# CAN_FB_V02.net
KiCad netlist of a schematic drawn in EAGLE
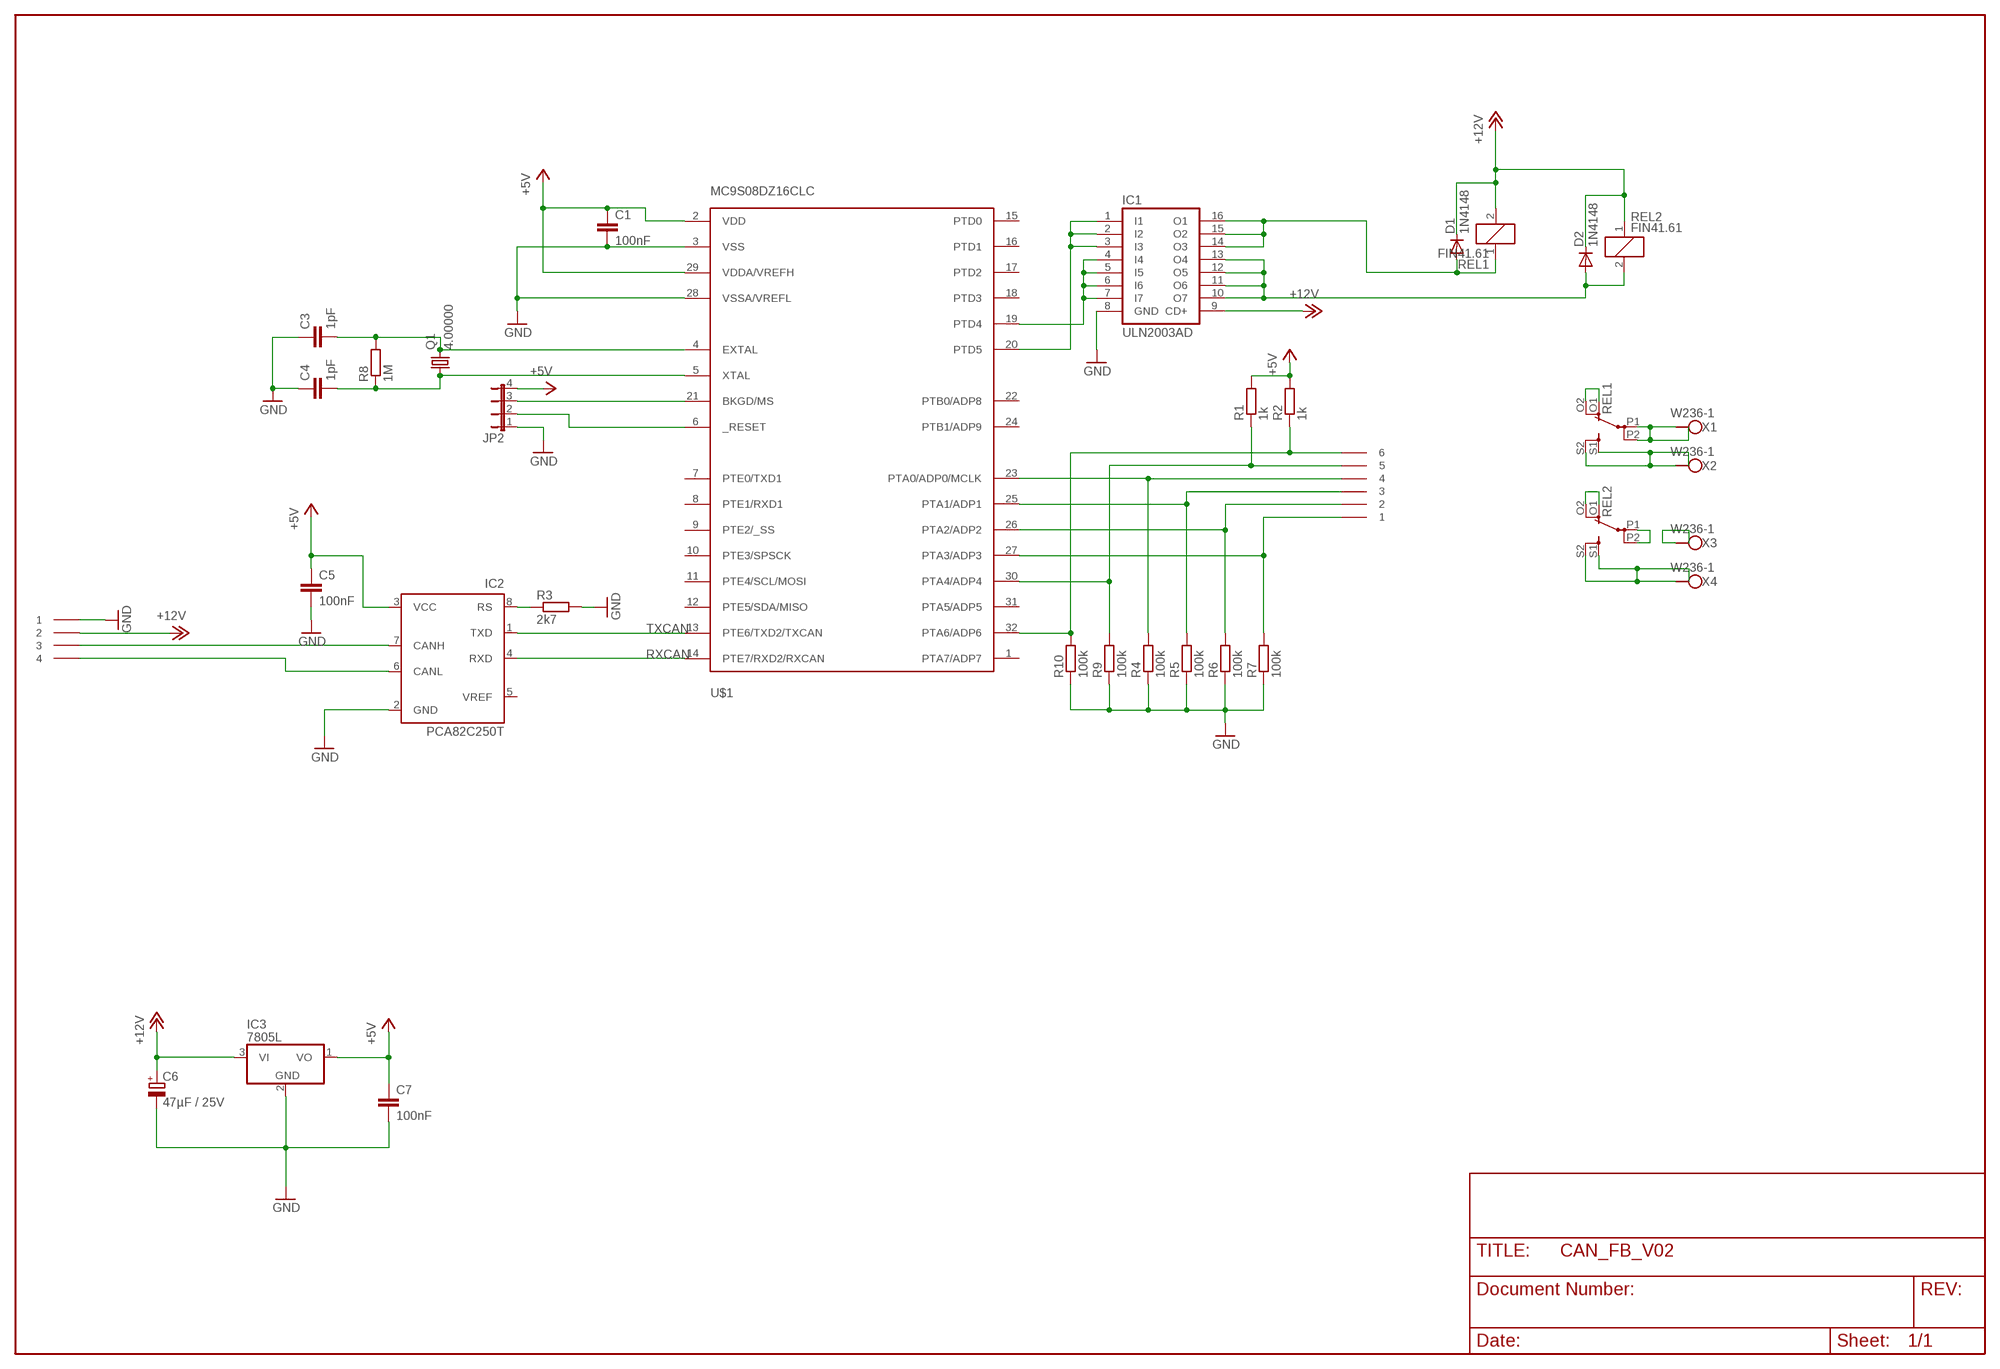
[diagram p0: schematic, sheet 1]

(export (version "E")
  (design (tool "Eeschema 10.0.6"))
  (components
    (comp (ref "C1")
      (value "100nF")
      (footprint "eagle-import:C0805K")
      (libsource (lib "eagle-import") (part "C-EUC0805K"))
    )
    (comp (ref "C3")
      (value "1pF")
      (footprint "eagle-import:C0805K")
      (libsource (lib "eagle-import") (part "C-EUC0805K"))
    )
    (comp (ref "C4")
      (value "1pF")
      (footprint "eagle-import:C0805K")
      (libsource (lib "eagle-import") (part "C-EUC0805K"))
    )
    (comp (ref "C5")
      (value "100nF")
      (footprint "eagle-import:C0805")
      (libsource (lib "eagle-import") (part "C-EUC0805"))
    )
    (comp (ref "C6")
      (value "47µF / 25V")
      (footprint "eagle-import:E2-5")
      (libsource (lib "eagle-import") (part "CPOL-EUE2-5"))
    )
    (comp (ref "C7")
      (value "100nF")
      (footprint "eagle-import:C0805K")
      (libsource (lib "eagle-import") (part "C-EUC0805K"))
    )
    (comp (ref "D1")
      (value "1N4148")
      (footprint "eagle-import:SOD80C")
      (libsource (lib "eagle-import") (part "DIODE-SOD80C"))
    )
    (comp (ref "D2")
      (value "1N4148")
      (footprint "eagle-import:SOD80C")
      (libsource (lib "eagle-import") (part "DIODE-SOD80C"))
    )
    (comp (ref "IC1")
      (value "ULN2003AD")
      (footprint "eagle-import:SO16")
      (libsource (lib "eagle-import") (part "ULN2003AD"))
    )
    (comp (ref "IC2")
      (value "PCA82C250T")
      (footprint "eagle-import:SO8")
      (libsource (lib "eagle-import") (part "PCA82C250T"))
    )
    (comp (ref "IC3")
      (value "7805L")
      (footprint "eagle-import:TO92")
      (libsource (lib "eagle-import") (part "78L05"))
    )
    (comp (ref "JP2")
      (value "JP4E")
      (footprint "eagle-import:JP4")
      (libsource (lib "eagle-import") (part "JP4E"))
    )
    (comp (ref "KL1")
      (value "AST021-04")
      (footprint "eagle-import:AST021-04")
      (libsource (lib "eagle-import") (part "AST021-04"))
    )
    (comp (ref "KL2")
      (value "AST021-06")
      (footprint "eagle-import:AST021-06")
      (libsource (lib "eagle-import") (part "AST021-06"))
    )
    (comp (ref "Q1")
      (value "4.00000")
      (footprint "eagle-import:HC49U-V")
      (libsource (lib "eagle-import") (part "CRYTALHC49U-V"))
    )
    (comp (ref "R1")
      (value "1k")
      (footprint "eagle-import:R0805")
      (libsource (lib "eagle-import") (part "R-EU_R0805"))
    )
    (comp (ref "R2")
      (value "1k")
      (footprint "eagle-import:R0805")
      (libsource (lib "eagle-import") (part "R-EU_R0805"))
    )
    (comp (ref "R3")
      (value "2k7")
      (footprint "eagle-import:R0805")
      (libsource (lib "eagle-import") (part "R-EU_R0805"))
    )
    (comp (ref "R4")
      (value "100k")
      (footprint "eagle-import:R0805")
      (libsource (lib "eagle-import") (part "R-EU_R0805"))
    )
    (comp (ref "R5")
      (value "100k")
      (footprint "eagle-import:R0805")
      (libsource (lib "eagle-import") (part "R-EU_R0805"))
    )
    (comp (ref "R6")
      (value "100k")
      (footprint "eagle-import:R0805")
      (libsource (lib "eagle-import") (part "R-EU_R0805"))
    )
    (comp (ref "R7")
      (value "100k")
      (footprint "eagle-import:R0805")
      (libsource (lib "eagle-import") (part "R-EU_R0805"))
    )
    (comp (ref "R8")
      (value "1M")
      (footprint "eagle-import:R0805")
      (libsource (lib "eagle-import") (part "R-EU_R0805"))
    )
    (comp (ref "R9")
      (value "100k")
      (footprint "eagle-import:R0805")
      (libsource (lib "eagle-import") (part "R-EU_R0805"))
    )
    (comp (ref "R10")
      (value "100k")
      (footprint "eagle-import:R0805")
      (libsource (lib "eagle-import") (part "R-EU_R0805"))
    )
    (comp (ref "REL1")
      (value "FIN41.61")
      (footprint "eagle-import:FIN41")
      (libsource (lib "eagle-import") (part "FIN41.61"))
    )
    (comp (ref "REL2")
      (value "FIN41.61")
      (footprint "eagle-import:FIN41")
      (libsource (lib "eagle-import") (part "FIN41.61"))
    )
    (comp (ref "U$1")
      (value "MC9S08DZ16CLC")
      (footprint "eagle-import:LQFP32")
      (libsource (lib "eagle-import") (part "MC9S08DZ16CLC"))
    )
    (comp (ref "X1")
      (value "W236-1")
      (footprint "eagle-import:W236-1")
      (libsource (lib "eagle-import") (part "W236-1"))
    )
    (comp (ref "X2")
      (value "W236-1")
      (footprint "eagle-import:W236-1")
      (libsource (lib "eagle-import") (part "W236-1"))
    )
    (comp (ref "X3")
      (value "W236-1")
      (footprint "eagle-import:W236-1")
      (libsource (lib "eagle-import") (part "W236-1"))
    )
    (comp (ref "X4")
      (value "W236-1")
      (footprint "eagle-import:W236-1")
      (libsource (lib "eagle-import") (part "W236-1"))
    )
  )
  (nets
    (net (code "1") (name "+5V") (class "Default")
      (node (ref "C1") (pin "1") (pinfunction "1_1") (pintype "passive"))
      (node (ref "C5") (pin "1") (pinfunction "1_1") (pintype "passive"))
      (node (ref "C7") (pin "1") (pinfunction "1_1") (pintype "passive"))
      (node (ref "IC2") (pin "3") (pinfunction "VCC_3") (pintype "power_in"))
      (node (ref "IC3") (pin "1") (pinfunction "VO_1") (pintype "passive"))
      (node (ref "JP2") (pin "4") (pinfunction "4_4") (pintype "passive"))
      (node (ref "R1") (pin "2") (pinfunction "2_2") (pintype "passive"))
      (node (ref "R2") (pin "2") (pinfunction "2_2") (pintype "passive"))
      (node (ref "U$1") (pin "2") (pinfunction "VDD_2") (pintype "power_in"))
      (node (ref "U$1") (pin "29") (pinfunction "VDDA/VREFH_29") (pintype "power_in"))
    )
    (net (code "2") (name "+12V") (class "Default")
      (node (ref "C6") (pin "+") (pinfunction "+_+") (pintype "passive"))
      (node (ref "D1") (pin "C") (pinfunction "C_C") (pintype "passive"))
      (node (ref "D2") (pin "C") (pinfunction "C_C") (pintype "passive"))
      (node (ref "IC1") (pin "9") (pinfunction "CD+_9") (pintype "passive"))
      (node (ref "IC3") (pin "3") (pinfunction "VI_3") (pintype "input"))
      (node (ref "KL1") (pin "P$2") (pinfunction "2_P$2") (pintype "bidirectional"))
      (node (ref "REL1") (pin "2") (pinfunction "2_2") (pintype "passive"))
      (node (ref "REL2") (pin "1") (pinfunction "1_1") (pintype "passive"))
    )
    (net (code "3") (name "/RXCAN") (class "Default")
      (node (ref "IC2") (pin "4") (pinfunction "RXD_4") (pintype "output"))
      (node (ref "U$1") (pin "14") (pinfunction "PTE7/RXD2/RXCAN_14") (pintype "input"))
    )
    (net (code "4") (name "/TXCAN") (class "Default")
      (node (ref "IC2") (pin "1") (pinfunction "TXD_1") (pintype "input"))
      (node (ref "U$1") (pin "13") (pinfunction "PTE6/TXD2/TXCAN_13") (pintype "output"))
    )
    (net (code "5") (name "GND") (class "Default")
      (node (ref "C1") (pin "2") (pinfunction "2_2") (pintype "passive"))
      (node (ref "C3") (pin "1") (pinfunction "1_1") (pintype "passive"))
      (node (ref "C4") (pin "1") (pinfunction "1_1") (pintype "passive"))
      (node (ref "C5") (pin "2") (pinfunction "2_2") (pintype "passive"))
      (node (ref "C6") (pin "-") (pinfunction "-_-") (pintype "passive"))
      (node (ref "C7") (pin "2") (pinfunction "2_2") (pintype "passive"))
      (node (ref "IC1") (pin "8") (pinfunction "GND_8") (pintype "power_in"))
      (node (ref "IC2") (pin "2") (pinfunction "GND_2") (pintype "power_in"))
      (node (ref "IC3") (pin "2") (pinfunction "GND_2") (pintype "passive"))
      (node (ref "JP2") (pin "1") (pinfunction "1_1") (pintype "passive"))
      (node (ref "KL1") (pin "P$1") (pinfunction "1_P$1") (pintype "bidirectional"))
      (node (ref "R10") (pin "1") (pinfunction "1_1") (pintype "passive"))
      (node (ref "R3") (pin "2") (pinfunction "2_2") (pintype "passive"))
      (node (ref "R4") (pin "1") (pinfunction "1_1") (pintype "passive"))
      (node (ref "R5") (pin "1") (pinfunction "1_1") (pintype "passive"))
      (node (ref "R6") (pin "1") (pinfunction "1_1") (pintype "passive"))
      (node (ref "R7") (pin "1") (pinfunction "1_1") (pintype "passive"))
      (node (ref "R9") (pin "1") (pinfunction "1_1") (pintype "passive"))
      (node (ref "U$1") (pin "28") (pinfunction "VSSA/VREFL_28") (pintype "power_in"))
      (node (ref "U$1") (pin "3") (pinfunction "VSS_3") (pintype "power_in"))
    )
    (net (code "6") (name "Net-(IC1-I1)") (class "Default")
      (node (ref "IC1") (pin "1") (pinfunction "I1_1") (pintype "input"))
      (node (ref "IC1") (pin "2") (pinfunction "I2_2") (pintype "input"))
      (node (ref "IC1") (pin "3") (pinfunction "I3_3") (pintype "input"))
      (node (ref "U$1") (pin "20") (pinfunction "PTD5_20") (pintype "bidirectional"))
    )
    (net (code "7") (name "Net-(IC1-I4)") (class "Default")
      (node (ref "IC1") (pin "4") (pinfunction "I4_4") (pintype "input"))
      (node (ref "IC1") (pin "5") (pinfunction "I5_5") (pintype "input"))
      (node (ref "IC1") (pin "6") (pinfunction "I6_6") (pintype "input"))
      (node (ref "IC1") (pin "7") (pinfunction "I7_7") (pintype "input"))
      (node (ref "U$1") (pin "19") (pinfunction "PTD4_19") (pintype "bidirectional"))
    )
    (net (code "8") (name "Net-(IC1-O1)") (class "Default")
      (node (ref "D1") (pin "A") (pinfunction "A_A") (pintype "passive"))
      (node (ref "IC1") (pin "14") (pinfunction "O3_14") (pintype "open_collector"))
      (node (ref "IC1") (pin "15") (pinfunction "O2_15") (pintype "open_collector"))
      (node (ref "IC1") (pin "16") (pinfunction "O1_16") (pintype "open_collector"))
      (node (ref "REL1") (pin "1") (pinfunction "1_1") (pintype "passive"))
    )
    (net (code "9") (name "Net-(IC1-O4)") (class "Default")
      (node (ref "D2") (pin "A") (pinfunction "A_A") (pintype "passive"))
      (node (ref "IC1") (pin "10") (pinfunction "O7_10") (pintype "open_collector"))
      (node (ref "IC1") (pin "11") (pinfunction "O6_11") (pintype "open_collector"))
      (node (ref "IC1") (pin "12") (pinfunction "O5_12") (pintype "open_collector"))
      (node (ref "IC1") (pin "13") (pinfunction "O4_13") (pintype "open_collector"))
      (node (ref "REL2") (pin "2") (pinfunction "2_2") (pintype "passive"))
    )
    (net (code "10") (name "Net-(IC2-CANH)") (class "Default")
      (node (ref "IC2") (pin "7") (pinfunction "CANH_7") (pintype "bidirectional"))
      (node (ref "KL1") (pin "P$3") (pinfunction "3_P$3") (pintype "bidirectional"))
    )
    (net (code "11") (name "Net-(IC2-CANL)") (class "Default")
      (node (ref "IC2") (pin "6") (pinfunction "CANL_6") (pintype "bidirectional"))
      (node (ref "KL1") (pin "P$4") (pinfunction "4_P$4") (pintype "bidirectional"))
    )
    (net (code "12") (name "Net-(IC2-RS)") (class "Default")
      (node (ref "IC2") (pin "8") (pinfunction "RS_8") (pintype "input"))
      (node (ref "R3") (pin "1") (pinfunction "1_1") (pintype "passive"))
    )
    (net (code "13") (name "Net-(KL2-1)") (class "Default")
      (node (ref "KL2") (pin "P$1") (pinfunction "1_P$1") (pintype "bidirectional"))
      (node (ref "R7") (pin "2") (pinfunction "2_2") (pintype "passive"))
      (node (ref "U$1") (pin "27") (pinfunction "PTA3/ADP3_27") (pintype "bidirectional"))
    )
    (net (code "14") (name "Net-(KL2-2)") (class "Default")
      (node (ref "KL2") (pin "P$2") (pinfunction "2_P$2") (pintype "bidirectional"))
      (node (ref "R6") (pin "2") (pinfunction "2_2") (pintype "passive"))
      (node (ref "U$1") (pin "26") (pinfunction "PTA2/ADP2_26") (pintype "bidirectional"))
    )
    (net (code "15") (name "Net-(KL2-3)") (class "Default")
      (node (ref "KL2") (pin "P$3") (pinfunction "3_P$3") (pintype "bidirectional"))
      (node (ref "R5") (pin "2") (pinfunction "2_2") (pintype "passive"))
      (node (ref "U$1") (pin "25") (pinfunction "PTA1/ADP1_25") (pintype "bidirectional"))
    )
    (net (code "16") (name "Net-(KL2-4)") (class "Default")
      (node (ref "KL2") (pin "P$4") (pinfunction "4_P$4") (pintype "bidirectional"))
      (node (ref "R4") (pin "2") (pinfunction "2_2") (pintype "passive"))
      (node (ref "U$1") (pin "23") (pinfunction "PTA0/ADP0/MCLK_23") (pintype "bidirectional"))
    )
    (net (code "17") (name "Net-(KL2-5)") (class "Default")
      (node (ref "KL2") (pin "P$5") (pinfunction "5_P$5") (pintype "bidirectional"))
      (node (ref "R1") (pin "1") (pinfunction "1_1") (pintype "passive"))
      (node (ref "R9") (pin "2") (pinfunction "2_2") (pintype "passive"))
      (node (ref "U$1") (pin "30") (pinfunction "PTA4/ADP4_30") (pintype "bidirectional"))
    )
    (net (code "18") (name "Net-(KL2-6)") (class "Default")
      (node (ref "KL2") (pin "P$6") (pinfunction "6_P$6") (pintype "bidirectional"))
      (node (ref "R10") (pin "2") (pinfunction "2_2") (pintype "passive"))
      (node (ref "R2") (pin "1") (pinfunction "1_1") (pintype "passive"))
      (node (ref "U$1") (pin "32") (pinfunction "PTA6/ADP6_32") (pintype "bidirectional"))
    )
    (net (code "19") (name "Net-(REL1B-O-PadO1)") (class "Default")
      (node (ref "REL1") (pin "O1") (pinfunction "O_O1") (pintype "passive"))
      (node (ref "REL1") (pin "O2") (pinfunction "O_O2") (pintype "passive"))
    )
    (net (code "20") (name "Net-(REL2B-O-PadO1)") (class "Default")
      (node (ref "REL2") (pin "O1") (pinfunction "O_O1") (pintype "passive"))
      (node (ref "REL2") (pin "O2") (pinfunction "O_O2") (pintype "passive"))
    )
    (net (code "21") (name "Net-(REL2B-P-PadP1)") (class "Default")
      (node (ref "REL2") (pin "P1") (pinfunction "P_P1") (pintype "passive"))
      (node (ref "REL2") (pin "P2") (pinfunction "P_P2") (pintype "passive"))
    )
    (net (code "22") (name "Net-(U$1-BKGD{slash}MS)") (class "Default")
      (node (ref "JP2") (pin "3") (pinfunction "3_3") (pintype "passive"))
      (node (ref "U$1") (pin "21") (pinfunction "BKGD/MS_21") (pintype "bidirectional"))
    )
    (net (code "23") (name "Net-(U$1-EXTAL)") (class "Default")
      (node (ref "C3") (pin "2") (pinfunction "2_2") (pintype "passive"))
      (node (ref "Q1") (pin "2") (pinfunction "2_2") (pintype "passive"))
      (node (ref "R8") (pin "2") (pinfunction "2_2") (pintype "passive"))
      (node (ref "U$1") (pin "4") (pinfunction "EXTAL_4") (pintype "bidirectional"))
    )
    (net (code "24") (name "Net-(U$1-XTAL)") (class "Default")
      (node (ref "C4") (pin "2") (pinfunction "2_2") (pintype "passive"))
      (node (ref "Q1") (pin "1") (pinfunction "1_1") (pintype "passive"))
      (node (ref "R8") (pin "1") (pinfunction "1_1") (pintype "passive"))
      (node (ref "U$1") (pin "5") (pinfunction "XTAL_5") (pintype "bidirectional"))
    )
    (net (code "25") (name "Net-(U$1-_RESET)") (class "Default")
      (node (ref "JP2") (pin "2") (pinfunction "2_2") (pintype "passive"))
      (node (ref "U$1") (pin "6") (pinfunction "_RESET_6") (pintype "bidirectional"))
    )
    (net (code "26") (name "Net-(X1-KL1)") (class "Default")
      (node (ref "REL1") (pin "P1") (pinfunction "P_P1") (pintype "passive"))
      (node (ref "REL1") (pin "P2") (pinfunction "P_P2") (pintype "passive"))
      (node (ref "X1") (pin "1") (pinfunction "KL1_1") (pintype "passive"))
      (node (ref "X1") (pin "2") (pinfunction "KL2_2") (pintype "bidirectional"))
    )
    (net (code "27") (name "Net-(X2-KL1)") (class "Default")
      (node (ref "REL1") (pin "S1") (pinfunction "S_S1") (pintype "passive"))
      (node (ref "REL1") (pin "S2") (pinfunction "S_S2") (pintype "passive"))
      (node (ref "X2") (pin "1") (pinfunction "KL1_1") (pintype "passive"))
      (node (ref "X2") (pin "2") (pinfunction "KL2_2") (pintype "bidirectional"))
    )
    (net (code "28") (name "Net-(X3-KL1)") (class "Default")
      (node (ref "X3") (pin "1") (pinfunction "KL1_1") (pintype "passive"))
      (node (ref "X3") (pin "2") (pinfunction "KL2_2") (pintype "bidirectional"))
    )
    (net (code "29") (name "Net-(X4-KL1)") (class "Default")
      (node (ref "REL2") (pin "S1") (pinfunction "S_S1") (pintype "passive"))
      (node (ref "REL2") (pin "S2") (pinfunction "S_S2") (pintype "passive"))
      (node (ref "X4") (pin "1") (pinfunction "KL1_1") (pintype "passive"))
      (node (ref "X4") (pin "2") (pinfunction "KL2_2") (pintype "bidirectional"))
    )
    (net (code "30") (name "unconnected-(IC2-VREF-Pad5)") (class "Default")
      (node (ref "IC2") (pin "5") (pinfunction "VREF_5") (pintype "output"))
    )
    (net (code "31") (name "unconnected-(U$1-PTA5{slash}ADP5-Pad31)") (class "Default")
      (node (ref "U$1") (pin "31") (pinfunction "PTA5/ADP5_31") (pintype "bidirectional"))
    )
    (net (code "32") (name "unconnected-(U$1-PTA7{slash}ADP7-Pad1)") (class "Default")
      (node (ref "U$1") (pin "1") (pinfunction "PTA7/ADP7_1") (pintype "bidirectional"))
    )
    (net (code "33") (name "unconnected-(U$1-PTB0{slash}ADP8-Pad22)") (class "Default")
      (node (ref "U$1") (pin "22") (pinfunction "PTB0/ADP8_22") (pintype "bidirectional"))
    )
    (net (code "34") (name "unconnected-(U$1-PTB1{slash}ADP9-Pad24)") (class "Default")
      (node (ref "U$1") (pin "24") (pinfunction "PTB1/ADP9_24") (pintype "bidirectional"))
    )
    (net (code "35") (name "unconnected-(U$1-PTD0-Pad15)") (class "Default")
      (node (ref "U$1") (pin "15") (pinfunction "PTD0_15") (pintype "bidirectional"))
    )
    (net (code "36") (name "unconnected-(U$1-PTD1-Pad16)") (class "Default")
      (node (ref "U$1") (pin "16") (pinfunction "PTD1_16") (pintype "bidirectional"))
    )
    (net (code "37") (name "unconnected-(U$1-PTD2-Pad17)") (class "Default")
      (node (ref "U$1") (pin "17") (pinfunction "PTD2_17") (pintype "bidirectional"))
    )
    (net (code "38") (name "unconnected-(U$1-PTD3-Pad18)") (class "Default")
      (node (ref "U$1") (pin "18") (pinfunction "PTD3_18") (pintype "bidirectional"))
    )
    (net (code "39") (name "unconnected-(U$1-PTE0{slash}TXD1-Pad7)") (class "Default")
      (node (ref "U$1") (pin "7") (pinfunction "PTE0/TXD1_7") (pintype "bidirectional"))
    )
    (net (code "40") (name "unconnected-(U$1-PTE1{slash}RXD1-Pad8)") (class "Default")
      (node (ref "U$1") (pin "8") (pinfunction "PTE1/RXD1_8") (pintype "bidirectional"))
    )
    (net (code "41") (name "unconnected-(U$1-PTE2{slash}_SS-Pad9)") (class "Default")
      (node (ref "U$1") (pin "9") (pinfunction "PTE2/_SS_9") (pintype "bidirectional"))
    )
    (net (code "42") (name "unconnected-(U$1-PTE3{slash}SPSCK-Pad10)") (class "Default")
      (node (ref "U$1") (pin "10") (pinfunction "PTE3/SPSCK_10") (pintype "bidirectional"))
    )
    (net (code "43") (name "unconnected-(U$1-PTE4{slash}SCL{slash}MOSI-Pad11)") (class "Default")
      (node (ref "U$1") (pin "11") (pinfunction "PTE4/SCL/MOSI_11") (pintype "bidirectional"))
    )
    (net (code "44") (name "unconnected-(U$1-PTE5{slash}SDA{slash}MISO-Pad12)") (class "Default")
      (node (ref "U$1") (pin "12") (pinfunction "PTE5/SDA/MISO_12") (pintype "bidirectional"))
    )
  )
)
